# Temperature_Measurement.net
KiCad netlist of a schematic drawn in Altium Designer
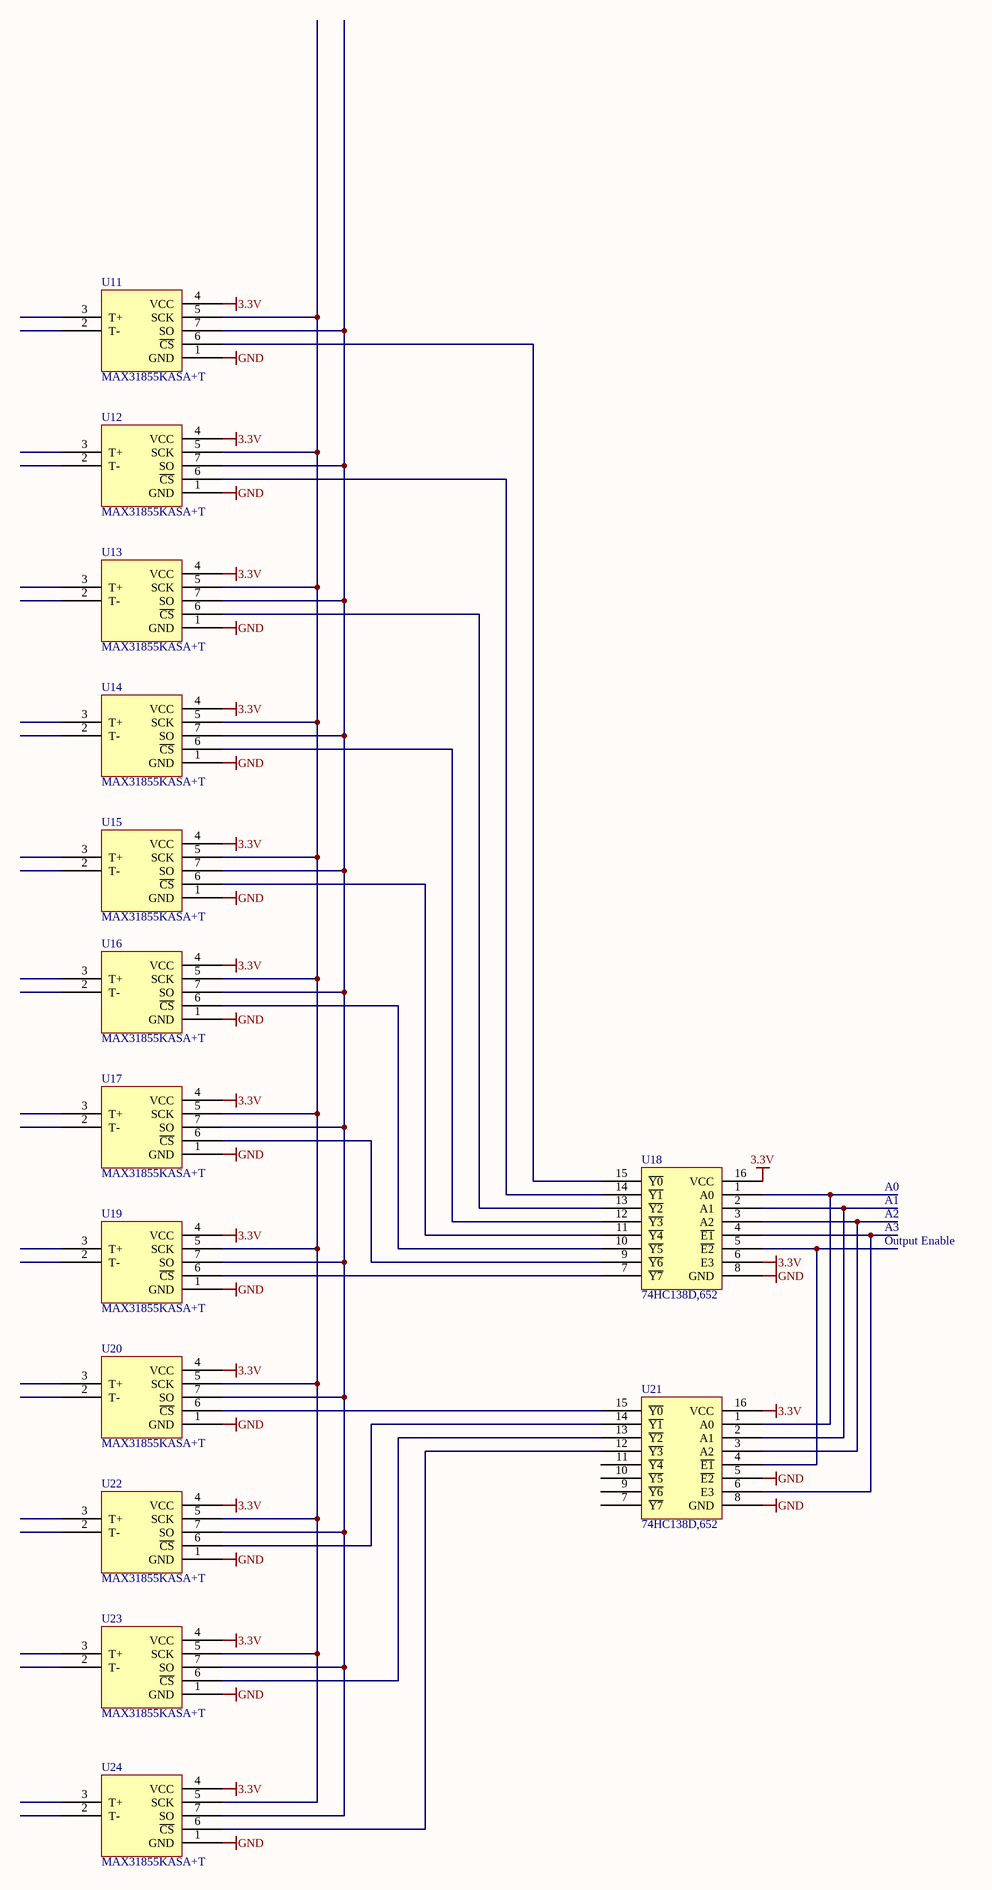
[diagram p0: Temperature Measurement.SchDoc]

(export (version "E")
  (design (tool "Eeschema 10.0.6"))
  (components
    (comp (ref "U11")
      (value "MAX31855KASA+T")
      (footprint "SOIC 8")
      (description "IC CONV THERMOCOUPLE-DGTL 8SOIC")
      (fields
        (field (name "MANUFACTURER") "Maxim Integrated")
        (field (name "MANUFACTURER PART NUMBER") "MAX31855KASA+T")
      )
      (libsource (lib "aIC") (part "MAX31855KASA+T"))
    )
    (comp (ref "U12")
      (value "MAX31855KASA+T")
      (footprint "SOIC 8")
      (description "IC CONV THERMOCOUPLE-DGTL 8SOIC")
      (fields
        (field (name "MANUFACTURER") "Maxim Integrated")
        (field (name "MANUFACTURER PART NUMBER") "MAX31855KASA+T")
      )
      (libsource (lib "aIC") (part "MAX31855KASA+T"))
    )
    (comp (ref "U13")
      (value "MAX31855KASA+T")
      (footprint "SOIC 8")
      (description "IC CONV THERMOCOUPLE-DGTL 8SOIC")
      (fields
        (field (name "MANUFACTURER") "Maxim Integrated")
        (field (name "MANUFACTURER PART NUMBER") "MAX31855KASA+T")
      )
      (libsource (lib "aIC") (part "MAX31855KASA+T"))
    )
    (comp (ref "U14")
      (value "MAX31855KASA+T")
      (footprint "SOIC 8")
      (description "IC CONV THERMOCOUPLE-DGTL 8SOIC")
      (fields
        (field (name "MANUFACTURER") "Maxim Integrated")
        (field (name "MANUFACTURER PART NUMBER") "MAX31855KASA+T")
      )
      (libsource (lib "aIC") (part "MAX31855KASA+T"))
    )
    (comp (ref "U15")
      (value "MAX31855KASA+T")
      (footprint "SOIC 8")
      (description "IC CONV THERMOCOUPLE-DGTL 8SOIC")
      (fields
        (field (name "MANUFACTURER") "Maxim Integrated")
        (field (name "MANUFACTURER PART NUMBER") "MAX31855KASA+T")
      )
      (libsource (lib "aIC") (part "MAX31855KASA+T"))
    )
    (comp (ref "U16")
      (value "MAX31855KASA+T")
      (footprint "SOIC 8")
      (description "IC CONV THERMOCOUPLE-DGTL 8SOIC")
      (fields
        (field (name "MANUFACTURER") "Maxim Integrated")
        (field (name "MANUFACTURER PART NUMBER") "MAX31855KASA+T")
      )
      (libsource (lib "aIC") (part "MAX31855KASA+T"))
    )
    (comp (ref "U17")
      (value "MAX31855KASA+T")
      (footprint "SOIC 8")
      (description "IC CONV THERMOCOUPLE-DGTL 8SOIC")
      (fields
        (field (name "MANUFACTURER") "Maxim Integrated")
        (field (name "MANUFACTURER PART NUMBER") "MAX31855KASA+T")
      )
      (libsource (lib "aIC") (part "MAX31855KASA+T"))
    )
    (comp (ref "U18")
      (value "74HC138D,652")
      (footprint "SOIC 16 Wide")
      (description "IC DECODER/DEMUX 3-8 LINE 16SOIC")
      (fields
        (field (name "MANUFACTURER") "NXP Semiconductors")
        (field (name "MANUFACTURER PART NUMBER") "74HC138D,652")
      )
      (libsource (lib "aIC") (part "74HC138D,652"))
    )
    (comp (ref "U19")
      (value "MAX31855KASA+T")
      (footprint "SOIC 8")
      (description "IC CONV THERMOCOUPLE-DGTL 8SOIC")
      (fields
        (field (name "MANUFACTURER") "Maxim Integrated")
        (field (name "MANUFACTURER PART NUMBER") "MAX31855KASA+T")
      )
      (libsource (lib "aIC") (part "MAX31855KASA+T"))
    )
    (comp (ref "U20")
      (value "MAX31855KASA+T")
      (footprint "SOIC 8")
      (description "IC CONV THERMOCOUPLE-DGTL 8SOIC")
      (fields
        (field (name "MANUFACTURER") "Maxim Integrated")
        (field (name "MANUFACTURER PART NUMBER") "MAX31855KASA+T")
      )
      (libsource (lib "aIC") (part "MAX31855KASA+T"))
    )
    (comp (ref "U21")
      (value "74HC138D,652")
      (footprint "SOIC 16 Wide")
      (description "IC DECODER/DEMUX 3-8 LINE 16SOIC")
      (fields
        (field (name "MANUFACTURER") "NXP Semiconductors")
        (field (name "MANUFACTURER PART NUMBER") "74HC138D,652")
      )
      (libsource (lib "aIC") (part "74HC138D,652"))
    )
    (comp (ref "U22")
      (value "MAX31855KASA+T")
      (footprint "SOIC 8")
      (description "IC CONV THERMOCOUPLE-DGTL 8SOIC")
      (fields
        (field (name "MANUFACTURER") "Maxim Integrated")
        (field (name "MANUFACTURER PART NUMBER") "MAX31855KASA+T")
      )
      (libsource (lib "aIC") (part "MAX31855KASA+T"))
    )
    (comp (ref "U23")
      (value "MAX31855KASA+T")
      (footprint "SOIC 8")
      (description "IC CONV THERMOCOUPLE-DGTL 8SOIC")
      (fields
        (field (name "MANUFACTURER") "Maxim Integrated")
        (field (name "MANUFACTURER PART NUMBER") "MAX31855KASA+T")
      )
      (libsource (lib "aIC") (part "MAX31855KASA+T"))
    )
    (comp (ref "U24")
      (value "MAX31855KASA+T")
      (footprint "SOIC 8")
      (description "IC CONV THERMOCOUPLE-DGTL 8SOIC")
      (fields
        (field (name "MANUFACTURER") "Maxim Integrated")
        (field (name "MANUFACTURER PART NUMBER") "MAX31855KASA+T")
      )
      (libsource (lib "aIC") (part "MAX31855KASA+T"))
    )
  )
  (nets
    (net (code "1") (name "3.3V") (class "Default")
      (node (ref "U11") (pin "4") (pinfunction "VCC_4") (pintype "passive"))
      (node (ref "U12") (pin "4") (pinfunction "VCC_4") (pintype "passive"))
      (node (ref "U13") (pin "4") (pinfunction "VCC_4") (pintype "passive"))
      (node (ref "U14") (pin "4") (pinfunction "VCC_4") (pintype "passive"))
      (node (ref "U15") (pin "4") (pinfunction "VCC_4") (pintype "passive"))
      (node (ref "U16") (pin "4") (pinfunction "VCC_4") (pintype "passive"))
      (node (ref "U17") (pin "4") (pinfunction "VCC_4") (pintype "passive"))
      (node (ref "U18") (pin "16") (pinfunction "VCC_16") (pintype "passive"))
      (node (ref "U18") (pin "6") (pinfunction "E3_6") (pintype "passive"))
      (node (ref "U19") (pin "4") (pinfunction "VCC_4") (pintype "passive"))
      (node (ref "U20") (pin "4") (pinfunction "VCC_4") (pintype "passive"))
      (node (ref "U21") (pin "16") (pinfunction "VCC_16") (pintype "passive"))
      (node (ref "U22") (pin "4") (pinfunction "VCC_4") (pintype "passive"))
      (node (ref "U23") (pin "4") (pinfunction "VCC_4") (pintype "passive"))
      (node (ref "U24") (pin "4") (pinfunction "VCC_4") (pintype "passive"))
    )
    (net (code "2") (name "GND") (class "Default")
      (node (ref "U11") (pin "1") (pinfunction "GND_1") (pintype "passive"))
      (node (ref "U12") (pin "1") (pinfunction "GND_1") (pintype "passive"))
      (node (ref "U13") (pin "1") (pinfunction "GND_1") (pintype "passive"))
      (node (ref "U14") (pin "1") (pinfunction "GND_1") (pintype "passive"))
      (node (ref "U15") (pin "1") (pinfunction "GND_1") (pintype "passive"))
      (node (ref "U16") (pin "1") (pinfunction "GND_1") (pintype "passive"))
      (node (ref "U17") (pin "1") (pinfunction "GND_1") (pintype "passive"))
      (node (ref "U18") (pin "8") (pinfunction "GND_8") (pintype "passive"))
      (node (ref "U19") (pin "1") (pinfunction "GND_1") (pintype "passive"))
      (node (ref "U20") (pin "1") (pinfunction "GND_1") (pintype "passive"))
      (node (ref "U21") (pin "5") (pinfunction "~{E2}_5") (pintype "passive"))
      (node (ref "U21") (pin "8") (pinfunction "GND_8") (pintype "passive"))
      (node (ref "U22") (pin "1") (pinfunction "GND_1") (pintype "passive"))
      (node (ref "U23") (pin "1") (pinfunction "GND_1") (pintype "passive"))
      (node (ref "U24") (pin "1") (pinfunction "GND_1") (pintype "passive"))
    )
    (net (code "3") (name "Net-(U11-SCK)") (class "Default")
      (node (ref "U11") (pin "5") (pinfunction "SCK_5") (pintype "passive"))
      (node (ref "U12") (pin "5") (pinfunction "SCK_5") (pintype "passive"))
      (node (ref "U13") (pin "5") (pinfunction "SCK_5") (pintype "passive"))
      (node (ref "U14") (pin "5") (pinfunction "SCK_5") (pintype "passive"))
      (node (ref "U15") (pin "5") (pinfunction "SCK_5") (pintype "passive"))
      (node (ref "U16") (pin "5") (pinfunction "SCK_5") (pintype "passive"))
      (node (ref "U17") (pin "5") (pinfunction "SCK_5") (pintype "passive"))
      (node (ref "U19") (pin "5") (pinfunction "SCK_5") (pintype "passive"))
      (node (ref "U20") (pin "5") (pinfunction "SCK_5") (pintype "passive"))
      (node (ref "U22") (pin "5") (pinfunction "SCK_5") (pintype "passive"))
      (node (ref "U23") (pin "5") (pinfunction "SCK_5") (pintype "passive"))
      (node (ref "U24") (pin "5") (pinfunction "SCK_5") (pintype "passive"))
    )
    (net (code "4") (name "Net-(U11-SO)") (class "Default")
      (node (ref "U11") (pin "7") (pinfunction "SO_7") (pintype "passive"))
      (node (ref "U12") (pin "7") (pinfunction "SO_7") (pintype "passive"))
      (node (ref "U13") (pin "7") (pinfunction "SO_7") (pintype "passive"))
      (node (ref "U14") (pin "7") (pinfunction "SO_7") (pintype "passive"))
      (node (ref "U15") (pin "7") (pinfunction "SO_7") (pintype "passive"))
      (node (ref "U16") (pin "7") (pinfunction "SO_7") (pintype "passive"))
      (node (ref "U17") (pin "7") (pinfunction "SO_7") (pintype "passive"))
      (node (ref "U19") (pin "7") (pinfunction "SO_7") (pintype "passive"))
      (node (ref "U20") (pin "7") (pinfunction "SO_7") (pintype "passive"))
      (node (ref "U22") (pin "7") (pinfunction "SO_7") (pintype "passive"))
      (node (ref "U23") (pin "7") (pinfunction "SO_7") (pintype "passive"))
      (node (ref "U24") (pin "7") (pinfunction "SO_7") (pintype "passive"))
    )
    (net (code "5") (name "Net-(U11-~{CS})") (class "Default")
      (node (ref "U11") (pin "6") (pinfunction "~{CS}_6") (pintype "passive"))
      (node (ref "U18") (pin "15") (pinfunction "~{Y0}_15") (pintype "passive"))
    )
    (net (code "6") (name "Net-(U12-~{CS})") (class "Default")
      (node (ref "U12") (pin "6") (pinfunction "~{CS}_6") (pintype "passive"))
      (node (ref "U18") (pin "14") (pinfunction "~{Y1}_14") (pintype "passive"))
    )
    (net (code "7") (name "Net-(U13-~{CS})") (class "Default")
      (node (ref "U13") (pin "6") (pinfunction "~{CS}_6") (pintype "passive"))
      (node (ref "U18") (pin "13") (pinfunction "~{Y2}_13") (pintype "passive"))
    )
    (net (code "8") (name "Net-(U14-~{CS})") (class "Default")
      (node (ref "U14") (pin "6") (pinfunction "~{CS}_6") (pintype "passive"))
      (node (ref "U18") (pin "12") (pinfunction "~{Y3}_12") (pintype "passive"))
    )
    (net (code "9") (name "Net-(U15-~{CS})") (class "Default")
      (node (ref "U15") (pin "6") (pinfunction "~{CS}_6") (pintype "passive"))
      (node (ref "U18") (pin "11") (pinfunction "~{Y4}_11") (pintype "passive"))
    )
    (net (code "10") (name "Net-(U16-~{CS})") (class "Default")
      (node (ref "U16") (pin "6") (pinfunction "~{CS}_6") (pintype "passive"))
      (node (ref "U18") (pin "10") (pinfunction "~{Y5}_10") (pintype "passive"))
    )
    (net (code "11") (name "Net-(U17-~{CS})") (class "Default")
      (node (ref "U17") (pin "6") (pinfunction "~{CS}_6") (pintype "passive"))
      (node (ref "U18") (pin "9") (pinfunction "~{Y6}_9") (pintype "passive"))
    )
    (net (code "12") (name "Net-(U18-A0)") (class "Default")
      (node (ref "U18") (pin "1") (pinfunction "A0_1") (pintype "passive"))
      (node (ref "U21") (pin "1") (pinfunction "A0_1") (pintype "passive"))
    )
    (net (code "13") (name "Net-(U18-A1)") (class "Default")
      (node (ref "U18") (pin "2") (pinfunction "A1_2") (pintype "passive"))
      (node (ref "U21") (pin "2") (pinfunction "A1_2") (pintype "passive"))
    )
    (net (code "14") (name "Net-(U18-A2)") (class "Default")
      (node (ref "U18") (pin "3") (pinfunction "A2_3") (pintype "passive"))
      (node (ref "U21") (pin "3") (pinfunction "A2_3") (pintype "passive"))
    )
    (net (code "15") (name "Net-(U18-~{E1})") (class "Default")
      (node (ref "U18") (pin "4") (pinfunction "~{E1}_4") (pintype "passive"))
      (node (ref "U21") (pin "6") (pinfunction "E3_6") (pintype "passive"))
    )
    (net (code "16") (name "Net-(U18-~{E2})") (class "Default")
      (node (ref "U18") (pin "5") (pinfunction "~{E2}_5") (pintype "passive"))
      (node (ref "U21") (pin "4") (pinfunction "~{E1}_4") (pintype "passive"))
    )
    (net (code "17") (name "Net-(U18-~{Y7})") (class "Default")
      (node (ref "U18") (pin "7") (pinfunction "~{Y7}_7") (pintype "passive"))
      (node (ref "U19") (pin "6") (pinfunction "~{CS}_6") (pintype "passive"))
    )
    (net (code "18") (name "Net-(U20-~{CS})") (class "Default")
      (node (ref "U20") (pin "6") (pinfunction "~{CS}_6") (pintype "passive"))
      (node (ref "U21") (pin "15") (pinfunction "~{Y0}_15") (pintype "passive"))
    )
    (net (code "19") (name "Net-(U21-~{Y1})") (class "Default")
      (node (ref "U21") (pin "14") (pinfunction "~{Y1}_14") (pintype "passive"))
      (node (ref "U22") (pin "6") (pinfunction "~{CS}_6") (pintype "passive"))
    )
    (net (code "20") (name "Net-(U21-~{Y2})") (class "Default")
      (node (ref "U21") (pin "13") (pinfunction "~{Y2}_13") (pintype "passive"))
      (node (ref "U23") (pin "6") (pinfunction "~{CS}_6") (pintype "passive"))
    )
    (net (code "21") (name "Net-(U21-~{Y3})") (class "Default")
      (node (ref "U21") (pin "12") (pinfunction "~{Y3}_12") (pintype "passive"))
      (node (ref "U24") (pin "6") (pinfunction "~{CS}_6") (pintype "passive"))
    )
    (net (code "22") (name "unconnected-(U11-T+-Pad3)") (class "Default")
      (node (ref "U11") (pin "3") (pinfunction "T+_3") (pintype "passive"))
    )
    (net (code "23") (name "unconnected-(U11-T--Pad2)") (class "Default")
      (node (ref "U11") (pin "2") (pinfunction "T-_2") (pintype "passive"))
    )
    (net (code "24") (name "unconnected-(U12-T+-Pad3)") (class "Default")
      (node (ref "U12") (pin "3") (pinfunction "T+_3") (pintype "passive"))
    )
    (net (code "25") (name "unconnected-(U12-T--Pad2)") (class "Default")
      (node (ref "U12") (pin "2") (pinfunction "T-_2") (pintype "passive"))
    )
    (net (code "26") (name "unconnected-(U13-T+-Pad3)") (class "Default")
      (node (ref "U13") (pin "3") (pinfunction "T+_3") (pintype "passive"))
    )
    (net (code "27") (name "unconnected-(U13-T--Pad2)") (class "Default")
      (node (ref "U13") (pin "2") (pinfunction "T-_2") (pintype "passive"))
    )
    (net (code "28") (name "unconnected-(U14-T+-Pad3)") (class "Default")
      (node (ref "U14") (pin "3") (pinfunction "T+_3") (pintype "passive"))
    )
    (net (code "29") (name "unconnected-(U14-T--Pad2)") (class "Default")
      (node (ref "U14") (pin "2") (pinfunction "T-_2") (pintype "passive"))
    )
    (net (code "30") (name "unconnected-(U15-T+-Pad3)") (class "Default")
      (node (ref "U15") (pin "3") (pinfunction "T+_3") (pintype "passive"))
    )
    (net (code "31") (name "unconnected-(U15-T--Pad2)") (class "Default")
      (node (ref "U15") (pin "2") (pinfunction "T-_2") (pintype "passive"))
    )
    (net (code "32") (name "unconnected-(U16-T+-Pad3)") (class "Default")
      (node (ref "U16") (pin "3") (pinfunction "T+_3") (pintype "passive"))
    )
    (net (code "33") (name "unconnected-(U16-T--Pad2)") (class "Default")
      (node (ref "U16") (pin "2") (pinfunction "T-_2") (pintype "passive"))
    )
    (net (code "34") (name "unconnected-(U17-T+-Pad3)") (class "Default")
      (node (ref "U17") (pin "3") (pinfunction "T+_3") (pintype "passive"))
    )
    (net (code "35") (name "unconnected-(U17-T--Pad2)") (class "Default")
      (node (ref "U17") (pin "2") (pinfunction "T-_2") (pintype "passive"))
    )
    (net (code "36") (name "unconnected-(U19-T+-Pad3)") (class "Default")
      (node (ref "U19") (pin "3") (pinfunction "T+_3") (pintype "passive"))
    )
    (net (code "37") (name "unconnected-(U19-T--Pad2)") (class "Default")
      (node (ref "U19") (pin "2") (pinfunction "T-_2") (pintype "passive"))
    )
    (net (code "38") (name "unconnected-(U20-T+-Pad3)") (class "Default")
      (node (ref "U20") (pin "3") (pinfunction "T+_3") (pintype "passive"))
    )
    (net (code "39") (name "unconnected-(U20-T--Pad2)") (class "Default")
      (node (ref "U20") (pin "2") (pinfunction "T-_2") (pintype "passive"))
    )
    (net (code "40") (name "unconnected-(U21-~{Y4}-Pad11)") (class "Default")
      (node (ref "U21") (pin "11") (pinfunction "~{Y4}_11") (pintype "passive"))
    )
    (net (code "41") (name "unconnected-(U21-~{Y5}-Pad10)") (class "Default")
      (node (ref "U21") (pin "10") (pinfunction "~{Y5}_10") (pintype "passive"))
    )
    (net (code "42") (name "unconnected-(U21-~{Y6}-Pad9)") (class "Default")
      (node (ref "U21") (pin "9") (pinfunction "~{Y6}_9") (pintype "passive"))
    )
    (net (code "43") (name "unconnected-(U21-~{Y7}-Pad7)") (class "Default")
      (node (ref "U21") (pin "7") (pinfunction "~{Y7}_7") (pintype "passive"))
    )
    (net (code "44") (name "unconnected-(U22-T+-Pad3)") (class "Default")
      (node (ref "U22") (pin "3") (pinfunction "T+_3") (pintype "passive"))
    )
    (net (code "45") (name "unconnected-(U22-T--Pad2)") (class "Default")
      (node (ref "U22") (pin "2") (pinfunction "T-_2") (pintype "passive"))
    )
    (net (code "46") (name "unconnected-(U23-T+-Pad3)") (class "Default")
      (node (ref "U23") (pin "3") (pinfunction "T+_3") (pintype "passive"))
    )
    (net (code "47") (name "unconnected-(U23-T--Pad2)") (class "Default")
      (node (ref "U23") (pin "2") (pinfunction "T-_2") (pintype "passive"))
    )
    (net (code "48") (name "unconnected-(U24-T+-Pad3)") (class "Default")
      (node (ref "U24") (pin "3") (pinfunction "T+_3") (pintype "passive"))
    )
    (net (code "49") (name "unconnected-(U24-T--Pad2)") (class "Default")
      (node (ref "U24") (pin "2") (pinfunction "T-_2") (pintype "passive"))
    )
  )
)
